# 08_ONB_COMPASS.net
KiCad netlist of a schematic drawn in Altium Designer
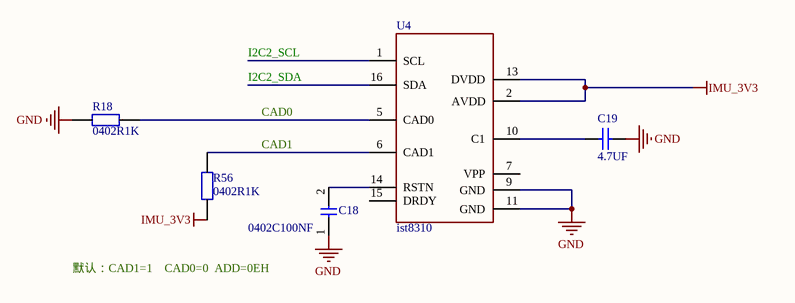
[diagram p0: 08_ONB_COMPASS.SchDoc]

(export (version "E")
  (design (tool "Eeschema 10.0.6"))
  (components
    (comp (ref "C18")
      (value "0402C100NF")
      (footprint "0402C")
      (description "50V 5%")
      (libsource (lib "CUAV") (part "0402C100NF"))
    )
    (comp (ref "C19")
      (value "4.7UF")
      (description "Capacitor")
      (libsource (lib "Miscellaneous Devices") (part "Cap"))
    )
    (comp (ref "R18")
      (value "0402R1K")
      (footprint "0402R")
      (description "0402R1K 1%")
      (libsource (lib "") (part "0402R1K_1"))
    )
    (comp (ref "R56")
      (value "0402R1K")
      (footprint "0402R")
      (description "0402R1K 1%")
      (libsource (lib "CUAV") (part "0402R1K"))
    )
    (comp (ref "U4") (value "ist8310") (footprint "LGA16_4X4") (libsource (lib "CUAV") (part "ist8310")))
  )
  (nets
    (net (code "1") (name "/CAD0") (class "Default")
      (node (ref "R18") (pin "1") (pintype "passive"))
      (node (ref "U4") (pin "5") (pinfunction "CAD0_5") (pintype "passive"))
    )
    (net (code "2") (name "/CAD1") (class "Default")
      (node (ref "R56") (pin "2") (pintype "passive"))
      (node (ref "U4") (pin "6") (pinfunction "CAD1_6") (pintype "passive"))
    )
    (net (code "3") (name "/I2C2_SCL") (class "Default")
      (node (ref "U4") (pin "1") (pinfunction "SCL_1") (pintype "passive"))
    )
    (net (code "4") (name "/I2C2_SDA") (class "Default")
      (node (ref "U4") (pin "16") (pinfunction "SDA_16") (pintype "passive"))
    )
    (net (code "6") (name "GND") (class "Default")
      (node (ref "C18") (pin "1") (pintype "passive"))
      (node (ref "C19") (pin "2") (pinfunction "2_2") (pintype "passive"))
      (node (ref "R18") (pin "2") (pintype "passive"))
      (node (ref "U4") (pin "11") (pinfunction "GND_11") (pintype "passive"))
      (node (ref "U4") (pin "9") (pinfunction "GND_9") (pintype "passive"))
    )
    (net (code "7") (name "IMU_3V3") (class "Default")
      (node (ref "R56") (pin "1") (pintype "passive"))
      (node (ref "U4") (pin "13") (pinfunction "DVDD_13") (pintype "passive"))
      (node (ref "U4") (pin "2") (pinfunction "AVDD_2") (pintype "passive"))
    )
    (net (code "8") (name "Net-(U4-C1)") (class "Default")
      (node (ref "C19") (pin "1") (pinfunction "1_1") (pintype "passive"))
      (node (ref "U4") (pin "10") (pinfunction "C1_10") (pintype "passive"))
    )
    (net (code "9") (name "Net-(U4-RSTN)") (class "Default")
      (node (ref "C18") (pin "2") (pintype "passive"))
      (node (ref "U4") (pin "14") (pinfunction "RSTN_14") (pintype "passive"))
    )
    (net (code "10") (name "unconnected-(U4-DRDY-Pad15)") (class "Default")
      (node (ref "U4") (pin "15") (pinfunction "DRDY_15") (pintype "passive"))
    )
    (net (code "11") (name "unconnected-(U4-VPP-Pad7)") (class "Default")
      (node (ref "U4") (pin "7") (pinfunction "VPP_7") (pintype "passive"))
    )
  )
)
